# URC_ezFET_Lite-USB.net
KiCad netlist of a schematic drawn in Altium Designer
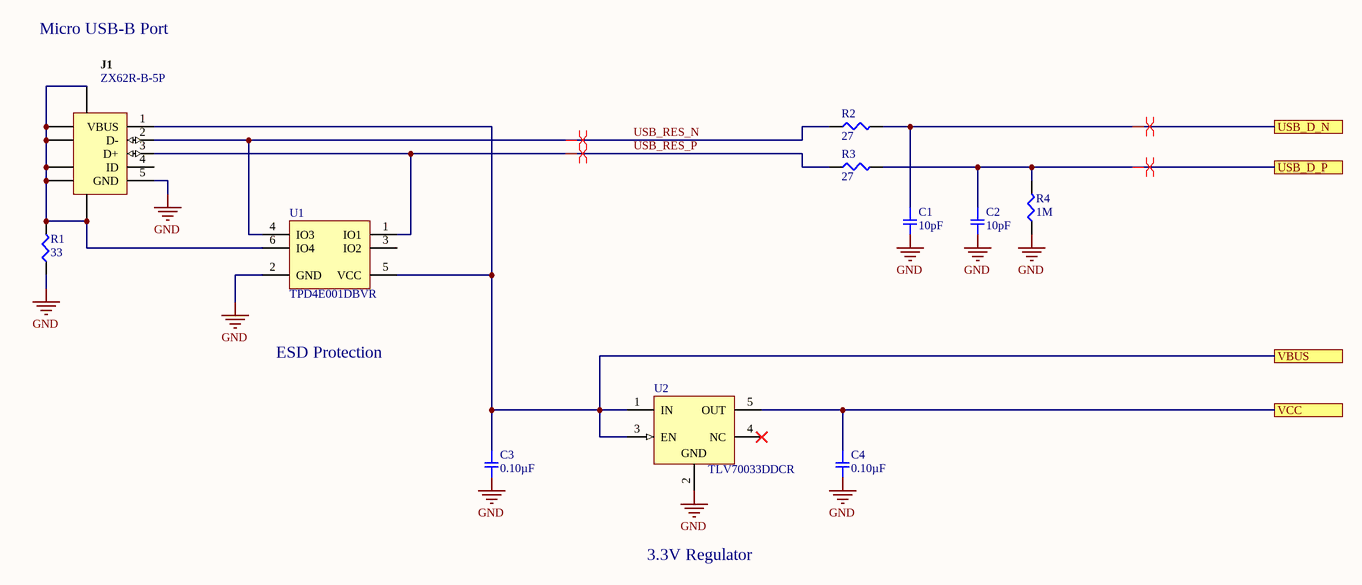
[diagram p0: URC_ezFET_Lite-USB.SchDoc]

(export (version "E")
  (design (tool "Eeschema 10.0.6"))
  (components
    (comp (ref "C1")
      (value "10pF")
      (footprint "SMD-1206C")
      (description "CAP CER 10PF 630V U2J 1206")
      (fields
        (field (name "DIGI-KEY PART NUMBER") "490-5037-1-ND")
        (field (name "PART NUMBER") "GCM31A7U2J100JX01D")
      )
      (libsource (lib "capacitor_murata_1206$") (part "GCM31A7U2J100JX01D"))
    )
    (comp (ref "C2")
      (value "10pF")
      (footprint "SMD-1206C")
      (description "CAP CER 10PF 630V U2J 1206")
      (fields
        (field (name "DIGI-KEY PART NUMBER") "490-5037-1-ND")
        (field (name "PART NUMBER") "GCM31A7U2J100JX01D")
      )
      (libsource (lib "capacitor_murata_1206$") (part "GCM31A7U2J100JX01D"))
    )
    (comp (ref "C3")
      (value "0.10µF")
      (footprint "SMD-1206C")
      (description "CAP CER 0.1UF 50V X7R 1206")
      (fields
        (field (name "DIGI-KEY PART NUMBER") "490-11166-1-ND")
        (field (name "PART NUMBER") "GCM319R71H104KA37D")
      )
      (libsource (lib "capacitor_murata_1206$") (part "GCM319R71H104KA37D"))
    )
    (comp (ref "C4")
      (value "0.10µF")
      (footprint "SMD-1206C")
      (description "CAP CER 0.1UF 50V X7R 1206")
      (fields
        (field (name "DIGI-KEY PART NUMBER") "490-11166-1-ND")
        (field (name "PART NUMBER") "GCM319R71H104KA37D")
      )
      (libsource (lib "capacitor_murata_1206$") (part "GCM319R71H104KA37D"))
    )
    (comp (ref "J1")
      (value "ZX62R-B-5P")
      (footprint "HIRO-ZX62R-B-5P_V")
      (description "Connector; USBMicro-B,Reverse type, SMT; 5 Position; Right Angle")
      (libsource (lib "Altium Content Vault") (part "HIRO-ZX62R-B-5P-5"))
    )
    (comp (ref "R1")
      (value "33")
      (footprint "SMD-0805-RES")
      (description "RES SMD 33 OHM 1% 1/8W 0805")
      (fields
        (field (name "PART NUMBER") "ERJ-6ENF33R0V")
        (field (name "DIGI-KEY PART NUMBER") "P33.0CCT-ND")
      )
      (libsource (lib "Panasonic_ERJ_0805") (part "ERJ-6ENF33R0V"))
    )
    (comp (ref "R2")
      (value "27")
      (footprint "SMD-0805-RES")
      (description "RES SMD 27 OHM 5% 1/2W 0805")
      (fields (field (name "PART NUMBER") "ERJ-P06J270V") (field (name "DIGI-KEY PART NUMBER") "P27ADCT-ND"))
      (libsource (lib "Panasonic_ERJ_0805") (part "ERJ-P06J270V"))
    )
    (comp (ref "R3")
      (value "27")
      (footprint "SMD-0805-RES")
      (description "RES SMD 27 OHM 5% 1/2W 0805")
      (fields (field (name "PART NUMBER") "ERJ-P06J270V") (field (name "DIGI-KEY PART NUMBER") "P27ADCT-ND"))
      (libsource (lib "Panasonic_ERJ_0805") (part "ERJ-P06J270V"))
    )
    (comp (ref "R4")
      (value "1M")
      (footprint "SMD-0805-RES")
      (description "RES SMD 1M OHM 5% 1/2W 0805")
      (fields
        (field (name "PART NUMBER") "ERJ-P06J105V")
        (field (name "DIGI-KEY PART NUMBER") "P1.0MADCT-ND")
      )
      (libsource (lib "Panasonic_ERJ_0805") (part "ERJ-P06J105V"))
    )
    (comp (ref "U1")
      (value "TPD4E001DBVR")
      (footprint "DBV0006A_M")
      (fields (field (name "MANUFACTURER") "Texas Instruments"))
      (libsource (lib "Altium Content Vault") (part "TI-TPD4E001-SOT-23_DBV-6"))
    )
    (comp (ref "U2")
      (value "TLV70033DDCR")
      (footprint "DDC0005A_M")
      (fields (field (name "MANUFACTURER") "Texas Instruments"))
      (libsource (lib "Altium Content Vault") (part "TI-TXX7XXXX-5"))
    )
  )
  (nets
    (net (code "1") (name "/USB_D_N") (class "Default")
      (node (ref "C1") (pin "1") (pinfunction "1_1") (pintype "passive"))
      (node (ref "R2") (pin "2") (pinfunction "2_2") (pintype "passive"))
    )
    (net (code "2") (name "/USB_D_P") (class "Default")
      (node (ref "C2") (pin "1") (pinfunction "1_1") (pintype "passive"))
      (node (ref "R3") (pin "2") (pinfunction "2_2") (pintype "passive"))
      (node (ref "R4") (pin "2") (pinfunction "2_2") (pintype "passive"))
    )
    (net (code "3") (name "/USB_RES_N") (class "Default")
      (node (ref "J1") (pin "2") (pinfunction "D-_2") (pintype "bidirectional"))
      (node (ref "R2") (pin "1") (pinfunction "1_1") (pintype "passive"))
      (node (ref "U1") (pin "4") (pinfunction "IO3_4") (pintype "passive"))
    )
    (net (code "4") (name "/USB_RES_P") (class "Default")
      (node (ref "J1") (pin "3") (pinfunction "D+_3") (pintype "bidirectional"))
      (node (ref "R3") (pin "1") (pinfunction "1_1") (pintype "passive"))
      (node (ref "U1") (pin "1") (pinfunction "IO1_1") (pintype "passive"))
    )
    (net (code "5") (name "/VBUS") (class "Default")
      (node (ref "C3") (pin "1") (pinfunction "1_1") (pintype "passive"))
      (node (ref "J1") (pin "1") (pinfunction "VBUS_1") (pintype "power_in"))
      (node (ref "U1") (pin "5") (pinfunction "VCC_5") (pintype "power_in"))
      (node (ref "U2") (pin "1") (pinfunction "IN_1") (pintype "power_in"))
      (node (ref "U2") (pin "3") (pinfunction "EN_3") (pintype "input"))
    )
    (net (code "6") (name "/VCC") (class "Default")
      (node (ref "C4") (pin "1") (pinfunction "1_1") (pintype "passive"))
      (node (ref "U2") (pin "5") (pinfunction "OUT_5") (pintype "power_in"))
    )
    (net (code "7") (name "GND") (class "Default")
      (node (ref "C1") (pin "2") (pinfunction "2_2") (pintype "passive"))
      (node (ref "C2") (pin "2") (pinfunction "2_2") (pintype "passive"))
      (node (ref "C3") (pin "2") (pinfunction "2_2") (pintype "passive"))
      (node (ref "C4") (pin "2") (pinfunction "2_2") (pintype "passive"))
      (node (ref "J1") (pin "5") (pinfunction "GND_5") (pintype "power_in"))
      (node (ref "R1") (pin "1") (pinfunction "1_1") (pintype "passive"))
      (node (ref "R4") (pin "1") (pinfunction "1_1") (pintype "passive"))
      (node (ref "U1") (pin "2") (pinfunction "GND_2") (pintype "power_in"))
      (node (ref "U2") (pin "2") (pinfunction "GND_2") (pintype "power_in"))
    )
    (net (code "8") (name "Net-(U1-IO4)") (class "Default")
      (node (ref "J1") (pin "10") (pinfunction "SHLD_10") (pintype "passive"))
      (node (ref "J1") (pin "11") (pinfunction "SHLD_11") (pintype "passive"))
      (node (ref "J1") (pin "6") (pinfunction "SHLD_6") (pintype "passive"))
      (node (ref "J1") (pin "7") (pinfunction "SHLD_7") (pintype "passive"))
      (node (ref "J1") (pin "8") (pinfunction "SHLD_8") (pintype "passive"))
      (node (ref "J1") (pin "9") (pinfunction "SHLD_9") (pintype "passive"))
      (node (ref "R1") (pin "2") (pinfunction "2_2") (pintype "passive"))
      (node (ref "U1") (pin "6") (pinfunction "IO4_6") (pintype "passive"))
    )
    (net (code "9") (name "unconnected-(J1-ID-Pad4)") (class "Default")
      (node (ref "J1") (pin "4") (pinfunction "ID_4") (pintype "passive"))
    )
    (net (code "10") (name "unconnected-(U1-IO2-Pad3)") (class "Default")
      (node (ref "U1") (pin "3") (pinfunction "IO2_3") (pintype "passive"))
    )
    (net (code "11") (name "unconnected-(U2-NC-Pad4)") (class "Default")
      (node (ref "U2") (pin "4") (pinfunction "NC_4") (pintype "passive+no_connect"))
    )
  )
)
